# atxmega.net
KiCad netlist of a schematic drawn in Altium Designer
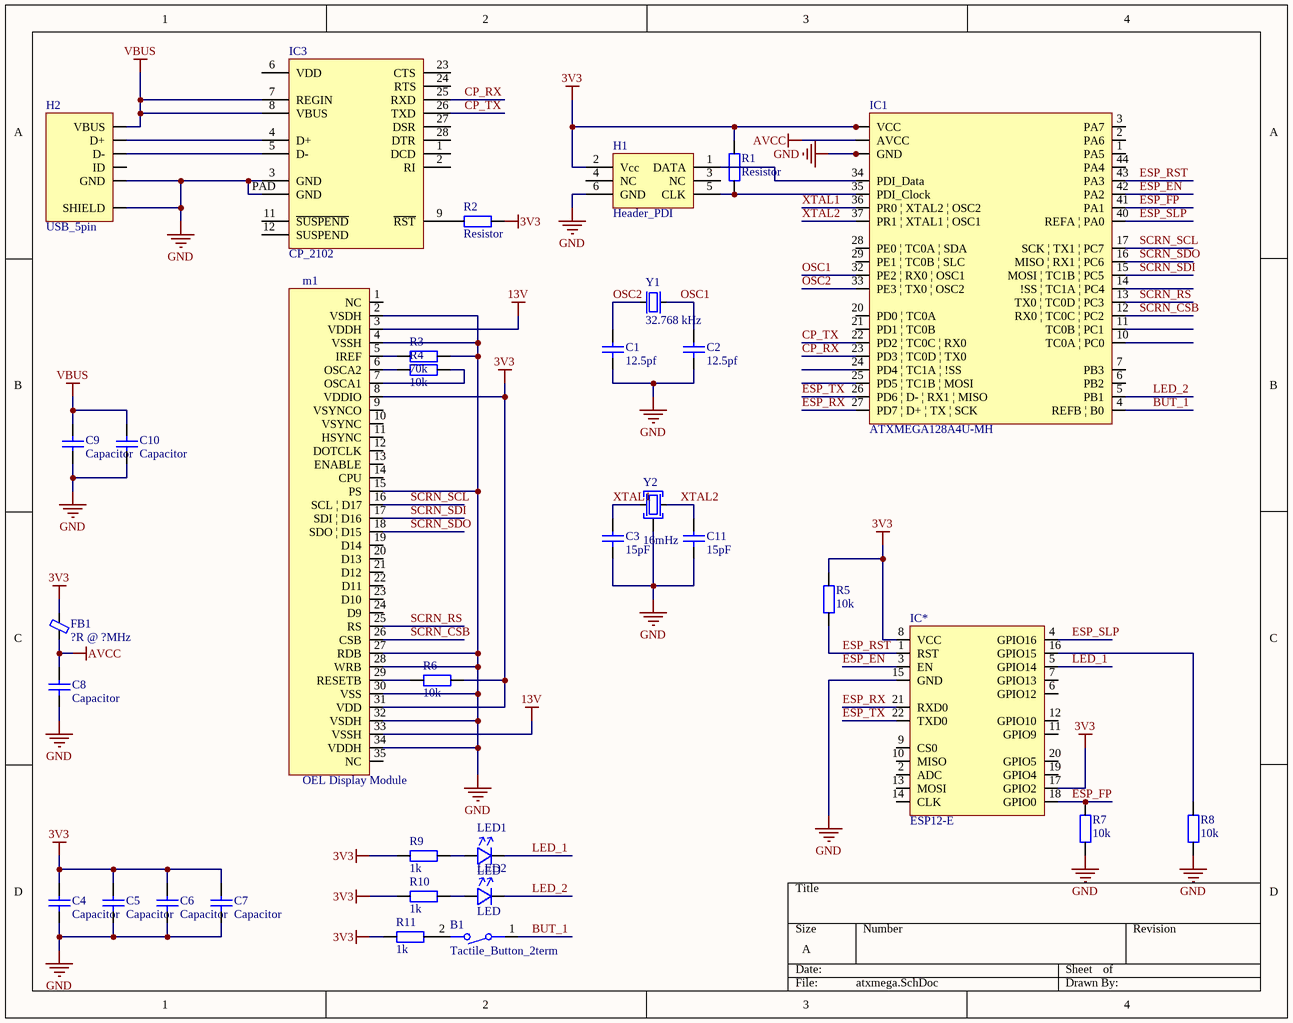
[diagram p0: atxmega.SchDoc]

(export (version "E")
  (design (tool "Eeschema 10.0.6"))
  (components
    (comp (ref "B1")
      (value "Tactile_Button_2term")
      (footprint "TACTILE_MINATUE_SMD_3.5x6mm")
      (libsource (lib "AranCustomFootprints") (part "Tactile_Button_2term"))
    )
    (comp (ref "C1")
      (value "12.5pf")
      (footprint "C0805")
      (description "Schematic symbol of a capacitor")
      (libsource (lib "AranCustomFootprints") (part "Capacitor"))
    )
    (comp (ref "C2")
      (value "12.5pf")
      (footprint "C0805")
      (description "Schematic symbol of a capacitor")
      (libsource (lib "AranCustomFootprints") (part "Capacitor"))
    )
    (comp (ref "C3")
      (value "15pF")
      (footprint "C0805")
      (description "Schematic symbol of a capacitor")
      (libsource (lib "AranCustomFootprints") (part "Capacitor"))
    )
    (comp (ref "C4")
      (value "Capacitor")
      (footprint "C0402")
      (description "Schematic symbol of a capacitor")
      (libsource (lib "AranCustomFootprints") (part "Capacitor"))
    )
    (comp (ref "C5")
      (value "Capacitor")
      (footprint "C0402")
      (description "Schematic symbol of a capacitor")
      (libsource (lib "AranCustomFootprints") (part "Capacitor"))
    )
    (comp (ref "C6")
      (value "Capacitor")
      (footprint "C0402")
      (description "Schematic symbol of a capacitor")
      (libsource (lib "AranCustomFootprints") (part "Capacitor"))
    )
    (comp (ref "C7")
      (value "Capacitor")
      (footprint "C0402")
      (description "Schematic symbol of a capacitor")
      (libsource (lib "AranCustomFootprints") (part "Capacitor"))
    )
    (comp (ref "C8")
      (value "Capacitor")
      (footprint "C0402")
      (description "Schematic symbol of a capacitor")
      (libsource (lib "AranCustomFootprints") (part "Capacitor"))
    )
    (comp (ref "C9")
      (value "Capacitor")
      (footprint "C0402")
      (description "Schematic symbol of a capacitor")
      (libsource (lib "AranCustomFootprints") (part "Capacitor"))
    )
    (comp (ref "C10")
      (value "Capacitor")
      (footprint "C0402")
      (description "Schematic symbol of a capacitor")
      (libsource (lib "AranCustomFootprints") (part "Capacitor"))
    )
    (comp (ref "C11")
      (value "15pF")
      (footprint "C0805")
      (description "Schematic symbol of a capacitor")
      (libsource (lib "AranCustomFootprints") (part "Capacitor"))
    )
    (comp (ref "FB1")
      (value "?R @ ?MHz")
      (footprint "L0805")
      (libsource (lib "AranCustomFootprints") (part "Ferrite"))
    )
    (comp (ref "H1")
      (value "Header_PDI")
      (footprint "6-HEADER_BOXED")
      (description "6-pin Boxed header with pinout used for PDI programming by Atmel programmers")
      (libsource (lib "AranCustomFootprints") (part "Header_PDI"))
    )
    (comp (ref "H2")
      (value "USB_5pin")
      (footprint "USB_Micro_B_RECEPTABLE_FCI")
      (description "5 Pins USB Connector")
      (libsource (lib "AranCustomFootprints") (part "USB_5pin"))
    )
    (comp (ref "IC*") (value "ESP12-E") (footprint "ESP12-E") (libsource (lib "elmarlib") (part "ESP12-E")))
    (comp (ref "IC1")
      (value "ATXMEGA128A4U-MH")
      (footprint "44-VFQFN-E")
      (description "AVR AVR® XMEGA® A4U Microcontroller IC 8/16-Bit 32MHz 128KB (64K x 16) FLASH 44-VQFN (7x7)")
      (libsource (lib "elmarlib") (part "ATXMEGA128A4U-MH"))
    )
    (comp (ref "IC3")
      (value "CP_2102")
      (footprint "28-QFN_Exposed_pad")
      (description "Single chip USB to UART Bridge")
      (libsource (lib "AranCustomFootprints") (part "CP_2102"))
    )
    (comp (ref "LED1")
      (value "LED")
      (footprint "0805_LED")
      (description "Schematic symbol of a LED")
      (libsource (lib "AranCustomFootprints") (part "LED"))
    )
    (comp (ref "LED2")
      (value "LED")
      (footprint "0805_LED")
      (description "Schematic symbol of a LED")
      (libsource (lib "AranCustomFootprints") (part "LED"))
    )
    (comp (ref "m1")
      (value "OEL Display Module")
      (footprint "FFC-35-pin-0.5")
      (description "Part ID: UG-6028GDEAF01")
      (libsource (lib "elmarlib") (part "OEL Display Module"))
    )
    (comp (ref "R1")
      (value "Resistor")
      (footprint "R0402")
      (description "Schematic symbol of a resistor")
      (libsource (lib "AranCustomFootprints") (part "Resistor"))
    )
    (comp (ref "R2")
      (value "Resistor")
      (footprint "R0402")
      (description "Schematic symbol of a resistor")
      (libsource (lib "AranCustomFootprints") (part "Resistor"))
    )
    (comp (ref "R3")
      (value "70k")
      (footprint "R0603")
      (description "Schematic symbol of a resistor")
      (libsource (lib "AranCustomFootprints") (part "Resistor"))
    )
    (comp (ref "R4")
      (value "10k")
      (footprint "R0603")
      (description "Schematic symbol of a resistor")
      (libsource (lib "AranCustomFootprints") (part "Resistor"))
    )
    (comp (ref "R5")
      (value "10k")
      (footprint "R0603")
      (description "Schematic symbol of a resistor")
      (libsource (lib "AranCustomFootprints") (part "Resistor"))
    )
    (comp (ref "R6")
      (value "10k")
      (footprint "R0603")
      (description "Schematic symbol of a resistor")
      (libsource (lib "AranCustomFootprints") (part "Resistor"))
    )
    (comp (ref "R7")
      (value "10k")
      (footprint "R0603")
      (description "Schematic symbol of a resistor")
      (libsource (lib "AranCustomFootprints") (part "Resistor"))
    )
    (comp (ref "R8")
      (value "10k")
      (footprint "R0603")
      (description "Schematic symbol of a resistor")
      (libsource (lib "AranCustomFootprints") (part "Resistor"))
    )
    (comp (ref "R9")
      (value "1k")
      (footprint "R0603")
      (description "Schematic symbol of a resistor")
      (libsource (lib "AranCustomFootprints") (part "Resistor"))
    )
    (comp (ref "R10")
      (value "1k")
      (footprint "R0603")
      (description "Schematic symbol of a resistor")
      (libsource (lib "AranCustomFootprints") (part "Resistor"))
    )
    (comp (ref "R11")
      (value "1k")
      (footprint "R0603")
      (description "Schematic symbol of a resistor")
      (libsource (lib "AranCustomFootprints") (part "Resistor"))
    )
    (comp (ref "Y1")
      (value "32.768 kHz")
      (footprint "4-SMD_FORK_CRYSTAL")
      (description "Schematic symbol of a 2pin crystal")
      (libsource (lib "AranCustomFootprints") (part "Crystal"))
    )
    (comp (ref "Y2")
      (value "16mHz")
      (footprint "Crystal_2.0x1.6")
      (description "Schematic symbol of a 2pin crystal with case connection")
      (libsource (lib "AranCustomFootprints") (part "Crystal_Ground"))
    )
  )
  (nets
    (net (code "1") (name "/BUT_1") (class "Default")
      (node (ref "B1") (pin "1") (pintype "passive"))
      (node (ref "IC1") (pin "4") (pinfunction "REFB_¦_B0_4") (pintype "passive"))
    )
    (net (code "2") (name "/CP_RX") (class "Default")
      (node (ref "IC1") (pin "23") (pinfunction "PD3_¦_TC0D_¦_TX0_23") (pintype "passive"))
      (node (ref "IC3") (pin "25") (pinfunction "RXD_25") (pintype "passive"))
    )
    (net (code "3") (name "/CP_TX") (class "Default")
      (node (ref "IC1") (pin "22") (pinfunction "PD2_¦_TC0C_¦_RX0_22") (pintype "passive"))
      (node (ref "IC3") (pin "26") (pinfunction "TXD_26") (pintype "passive"))
    )
    (net (code "4") (name "/ESP_EN") (class "Default")
      (node (ref "IC*") (pin "3") (pinfunction "EN_3") (pintype "passive"))
      (node (ref "IC1") (pin "42") (pinfunction "PA2_42") (pintype "passive"))
    )
    (net (code "5") (name "/ESP_FP") (class "Default")
      (node (ref "IC*") (pin "18") (pinfunction "GPIO0_18") (pintype "passive"))
      (node (ref "IC1") (pin "41") (pinfunction "PA1_41") (pintype "passive"))
      (node (ref "R7") (pin "1") (pinfunction "1_1") (pintype "passive"))
    )
    (net (code "6") (name "/ESP_RST") (class "Default")
      (node (ref "IC*") (pin "1") (pinfunction "RST_1") (pintype "passive"))
      (node (ref "IC1") (pin "43") (pinfunction "PA3_43") (pintype "passive"))
      (node (ref "R5") (pin "2") (pinfunction "2_2") (pintype "passive"))
    )
    (net (code "7") (name "/ESP_RX") (class "Default")
      (node (ref "IC*") (pin "21") (pinfunction "RXD0_21") (pintype "passive"))
      (node (ref "IC1") (pin "27") (pinfunction "PD7_¦_D+_¦_TX_¦_SCK_27") (pintype "passive"))
    )
    (net (code "8") (name "/ESP_SLP") (class "Default")
      (node (ref "IC*") (pin "4") (pinfunction "GPIO16_4") (pintype "passive"))
      (node (ref "IC1") (pin "40") (pinfunction "REFA_¦_PA0_40") (pintype "passive"))
    )
    (net (code "9") (name "/ESP_TX") (class "Default")
      (node (ref "IC*") (pin "22") (pinfunction "TXD0_22") (pintype "passive"))
      (node (ref "IC1") (pin "26") (pinfunction "PD6_¦_D-_¦_RX1_¦_MISO_26") (pintype "passive"))
    )
    (net (code "10") (name "/LED_1") (class "Default")
      (node (ref "IC*") (pin "5") (pinfunction "GPIO14_5") (pintype "passive"))
      (node (ref "LED1") (pin "C") (pinfunction "Cathode_C") (pintype "passive"))
    )
    (net (code "11") (name "/LED_2") (class "Default")
      (node (ref "IC1") (pin "5") (pinfunction "PB1_5") (pintype "passive"))
      (node (ref "LED2") (pin "C") (pinfunction "Cathode_C") (pintype "passive"))
    )
    (net (code "12") (name "/OSC1") (class "Default")
      (node (ref "C2") (pin "1") (pinfunction "1_1") (pintype "passive"))
      (node (ref "IC1") (pin "32") (pinfunction "PE2_¦_RX0_¦_OSC1_32") (pintype "passive"))
      (node (ref "Y1") (pin "1") (pinfunction "1_1") (pintype "passive"))
    )
    (net (code "13") (name "/OSC2") (class "Default")
      (node (ref "C1") (pin "1") (pinfunction "1_1") (pintype "passive"))
      (node (ref "IC1") (pin "33") (pinfunction "PE3_¦_TX0_¦_OSC2_33") (pintype "passive"))
      (node (ref "Y1") (pin "2") (pinfunction "2_2") (pintype "passive"))
    )
    (net (code "14") (name "/SCRN_CSB") (class "Default")
      (node (ref "IC1") (pin "12") (pinfunction "RX0_¦_TC0C_¦_PC2_12") (pintype "passive"))
      (node (ref "m1") (pin "26") (pinfunction "CSB_26") (pintype "passive"))
    )
    (net (code "15") (name "/SCRN_RS") (class "Default")
      (node (ref "IC1") (pin "13") (pinfunction "TX0_¦_TC0D_¦_PC3_13") (pintype "passive"))
      (node (ref "m1") (pin "25") (pinfunction "RS_25") (pintype "passive"))
    )
    (net (code "16") (name "/SCRN_SCL") (class "Default")
      (node (ref "IC1") (pin "17") (pinfunction "SCK_¦_TX1_¦_PC7_17") (pintype "passive"))
      (node (ref "m1") (pin "16") (pinfunction "SCL_¦_D17_16") (pintype "passive"))
    )
    (net (code "17") (name "/SCRN_SDI") (class "Default")
      (node (ref "IC1") (pin "15") (pinfunction "MOSI_¦_TC1B_¦_PC5_15") (pintype "passive"))
      (node (ref "m1") (pin "17") (pinfunction "SDI_¦_D16_17") (pintype "passive"))
    )
    (net (code "18") (name "/SCRN_SDO") (class "Default")
      (node (ref "IC1") (pin "16") (pinfunction "MISO_¦_RX1_¦_PC6_16") (pintype "passive"))
      (node (ref "m1") (pin "18") (pinfunction "SDO_¦_D15_18") (pintype "passive"))
    )
    (net (code "19") (name "/XTAL1") (class "Default")
      (node (ref "C3") (pin "1") (pinfunction "1_1") (pintype "passive"))
      (node (ref "IC1") (pin "36") (pinfunction "PR0_¦_XTAL2_¦_OSC2_36") (pintype "passive"))
      (node (ref "Y2") (pin "1") (pinfunction "1_1") (pintype "passive"))
    )
    (net (code "20") (name "/XTAL2") (class "Default")
      (node (ref "C11") (pin "1") (pinfunction "1_1") (pintype "passive"))
      (node (ref "IC1") (pin "37") (pinfunction "PR1_¦_XTAL1_¦_OSC1_37") (pintype "passive"))
      (node (ref "Y2") (pin "3") (pinfunction "3_3") (pintype "passive"))
    )
    (net (code "21") (name "3V3") (class "Default")
      (node (ref "C4") (pin "1") (pinfunction "1_1") (pintype "passive"))
      (node (ref "C5") (pin "1") (pinfunction "1_1") (pintype "passive"))
      (node (ref "C6") (pin "1") (pinfunction "1_1") (pintype "passive"))
      (node (ref "C7") (pin "1") (pinfunction "1_1") (pintype "passive"))
      (node (ref "FB1") (pin "2") (pinfunction "2_2") (pintype "passive"))
      (node (ref "H1") (pin "2") (pinfunction "Vcc_2") (pintype "passive"))
      (node (ref "IC*") (pin "17") (pinfunction "GPIO2_17") (pintype "passive"))
      (node (ref "IC*") (pin "8") (pinfunction "VCC_8") (pintype "passive"))
      (node (ref "IC1") (pin "19") (pinfunction "VCC_19") (pintype "passive"))
      (node (ref "IC1") (pin "31") (pinfunction "VCC_31") (pintype "passive"))
      (node (ref "IC1") (pin "9") (pinfunction "VCC_9") (pintype "passive"))
      (node (ref "R1") (pin "1") (pinfunction "1_1") (pintype "passive"))
      (node (ref "R10") (pin "1") (pinfunction "1_1") (pintype "passive"))
      (node (ref "R11") (pin "1") (pinfunction "1_1") (pintype "passive"))
      (node (ref "R2") (pin "1") (pinfunction "1_1") (pintype "passive"))
      (node (ref "R5") (pin "1") (pinfunction "1_1") (pintype "passive"))
      (node (ref "R6") (pin "1") (pinfunction "1_1") (pintype "passive"))
      (node (ref "R9") (pin "1") (pinfunction "1_1") (pintype "passive"))
      (node (ref "m1") (pin "31") (pinfunction "VDD_31") (pintype "passive"))
      (node (ref "m1") (pin "8") (pinfunction "VDDIO_8") (pintype "passive"))
    )
    (net (code "22") (name "13V") (class "Default")
      (node (ref "m1") (pin "3") (pinfunction "VDDH_3") (pintype "passive"))
      (node (ref "m1") (pin "33") (pinfunction "VSSH_33") (pintype "passive"))
    )
    (net (code "23") (name "AVCC") (class "Default")
      (node (ref "C8") (pin "1") (pinfunction "1_1") (pintype "passive"))
      (node (ref "FB1") (pin "1") (pinfunction "1_1") (pintype "passive"))
      (node (ref "IC1") (pin "39") (pinfunction "AVCC_39") (pintype "passive"))
    )
    (net (code "24") (name "GND") (class "Default")
      (node (ref "C1") (pin "2") (pinfunction "2_2") (pintype "passive"))
      (node (ref "C10") (pin "1") (pinfunction "1_1") (pintype "passive"))
      (node (ref "C11") (pin "2") (pinfunction "2_2") (pintype "passive"))
      (node (ref "C2") (pin "2") (pinfunction "2_2") (pintype "passive"))
      (node (ref "C3") (pin "2") (pinfunction "2_2") (pintype "passive"))
      (node (ref "C4") (pin "2") (pinfunction "2_2") (pintype "passive"))
      (node (ref "C5") (pin "2") (pinfunction "2_2") (pintype "passive"))
      (node (ref "C6") (pin "2") (pinfunction "2_2") (pintype "passive"))
      (node (ref "C7") (pin "2") (pinfunction "2_2") (pintype "passive"))
      (node (ref "C8") (pin "2") (pinfunction "2_2") (pintype "passive"))
      (node (ref "C9") (pin "1") (pinfunction "1_1") (pintype "passive"))
      (node (ref "H1") (pin "6") (pinfunction "GND_6") (pintype "passive"))
      (node (ref "H2") (pin "5") (pinfunction "GND_5") (pintype "passive"))
      (node (ref "H2") (pin "SHIELD") (pinfunction "SHIELD_SHIELD") (pintype "passive"))
      (node (ref "IC*") (pin "15") (pinfunction "GND_15") (pintype "passive"))
      (node (ref "IC1") (pin "18") (pinfunction "GND_18") (pintype "passive"))
      (node (ref "IC1") (pin "30") (pinfunction "GND_30") (pintype "passive"))
      (node (ref "IC1") (pin "38") (pinfunction "GND_38") (pintype "passive"))
      (node (ref "IC1") (pin "45") (pinfunction "GND_45") (pintype "passive"))
      (node (ref "IC1") (pin "8") (pinfunction "GND_8") (pintype "passive"))
      (node (ref "IC3") (pin "3") (pinfunction "GND_3") (pintype "passive"))
      (node (ref "IC3") (pin "PAD") (pinfunction "GND_PAD") (pintype "passive"))
      (node (ref "R3") (pin "1") (pinfunction "1_1") (pintype "passive"))
      (node (ref "R7") (pin "2") (pinfunction "2_2") (pintype "passive"))
      (node (ref "R8") (pin "2") (pinfunction "2_2") (pintype "passive"))
      (node (ref "Y2") (pin "2") (pinfunction "2_2") (pintype "passive"))
      (node (ref "m1") (pin "15") (pinfunction "PS_15") (pintype "passive"))
      (node (ref "m1") (pin "2") (pinfunction "VSDH_2") (pintype "passive"))
      (node (ref "m1") (pin "27") (pinfunction "RDB_27") (pintype "passive"))
      (node (ref "m1") (pin "28") (pinfunction "WRB_28") (pintype "passive"))
      (node (ref "m1") (pin "30") (pinfunction "VSS_30") (pintype "passive"))
      (node (ref "m1") (pin "32") (pinfunction "VSDH_32") (pintype "passive"))
      (node (ref "m1") (pin "34") (pinfunction "VDDH_34") (pintype "passive"))
      (node (ref "m1") (pin "4") (pinfunction "VSSH_4") (pintype "passive"))
    )
    (net (code "25") (name "Net-(B1-Pad2)") (class "Default")
      (node (ref "B1") (pin "2") (pintype "passive"))
      (node (ref "R11") (pin "2") (pinfunction "2_2") (pintype "passive"))
    )
    (net (code "26") (name "Net-(H1-CLK)") (class "Default")
      (node (ref "H1") (pin "5") (pinfunction "CLK_5") (pintype "passive"))
      (node (ref "IC1") (pin "35") (pinfunction "PDI_Clock_35") (pintype "passive"))
      (node (ref "R1") (pin "2") (pinfunction "2_2") (pintype "passive"))
    )
    (net (code "27") (name "Net-(H1-DATA)") (class "Default")
      (node (ref "H1") (pin "1") (pinfunction "DATA_1") (pintype "passive"))
      (node (ref "IC1") (pin "34") (pinfunction "PDI_Data_34") (pintype "passive"))
    )
    (net (code "28") (name "Net-(H2-D+)") (class "Default")
      (node (ref "H2") (pin "3") (pinfunction "D+_3") (pintype "passive"))
      (node (ref "IC3") (pin "4") (pinfunction "D+_4") (pintype "passive"))
    )
    (net (code "29") (name "Net-(H2-D-)") (class "Default")
      (node (ref "H2") (pin "2") (pinfunction "D-_2") (pintype "passive"))
      (node (ref "IC3") (pin "5") (pinfunction "D-_5") (pintype "passive"))
    )
    (net (code "30") (name "Net-(IC*-GPIO15)") (class "Default")
      (node (ref "IC*") (pin "16") (pinfunction "GPIO15_16") (pintype "passive"))
      (node (ref "R8") (pin "1") (pinfunction "1_1") (pintype "passive"))
    )
    (net (code "31") (name "Net-(IC3-~{RST})") (class "Default")
      (node (ref "IC3") (pin "9") (pinfunction "~{RST}_9") (pintype "passive"))
      (node (ref "R2") (pin "2") (pinfunction "2_2") (pintype "passive"))
    )
    (net (code "32") (name "Net-(LED1-Anode)") (class "Default")
      (node (ref "LED1") (pin "A") (pinfunction "Anode_A") (pintype "passive"))
      (node (ref "R9") (pin "2") (pinfunction "2_2") (pintype "passive"))
    )
    (net (code "33") (name "Net-(LED2-Anode)") (class "Default")
      (node (ref "LED2") (pin "A") (pinfunction "Anode_A") (pintype "passive"))
      (node (ref "R10") (pin "2") (pinfunction "2_2") (pintype "passive"))
    )
    (net (code "34") (name "Net-(m1-IREF)") (class "Default")
      (node (ref "R3") (pin "2") (pinfunction "2_2") (pintype "passive"))
      (node (ref "m1") (pin "5") (pinfunction "IREF_5") (pintype "passive"))
    )
    (net (code "35") (name "Net-(m1-OSCA1)") (class "Default")
      (node (ref "R4") (pin "1") (pinfunction "1_1") (pintype "passive"))
      (node (ref "m1") (pin "7") (pinfunction "OSCA1_7") (pintype "passive"))
    )
    (net (code "36") (name "Net-(m1-OSCA2)") (class "Default")
      (node (ref "R4") (pin "2") (pinfunction "2_2") (pintype "passive"))
      (node (ref "m1") (pin "6") (pinfunction "OSCA2_6") (pintype "passive"))
    )
    (net (code "37") (name "Net-(m1-RESETB)") (class "Default")
      (node (ref "R6") (pin "2") (pinfunction "2_2") (pintype "passive"))
      (node (ref "m1") (pin "29") (pinfunction "RESETB_29") (pintype "passive"))
    )
    (net (code "38") (name "VBUS") (class "Default")
      (node (ref "C10") (pin "2") (pinfunction "2_2") (pintype "passive"))
      (node (ref "C9") (pin "2") (pinfunction "2_2") (pintype "passive"))
      (node (ref "H2") (pin "1") (pinfunction "VBUS_1") (pintype "passive"))
      (node (ref "IC3") (pin "7") (pinfunction "REGIN_7") (pintype "passive"))
      (node (ref "IC3") (pin "8") (pinfunction "VBUS_8") (pintype "passive"))
    )
    (net (code "39") (name "unconnected-(H1-NC-Pad3)") (class "Default")
      (node (ref "H1") (pin "3") (pinfunction "NC_3") (pintype "passive"))
    )
    (net (code "40") (name "unconnected-(H1-NC-Pad4)") (class "Default")
      (node (ref "H1") (pin "4") (pinfunction "NC_4") (pintype "passive"))
    )
    (net (code "41") (name "unconnected-(H2-ID-Pad4)") (class "Default")
      (node (ref "H2") (pin "4") (pinfunction "ID_4") (pintype "passive"))
    )
    (net (code "42") (name "unconnected-(IC*-ADC-Pad2)") (class "Default")
      (node (ref "IC*") (pin "2") (pinfunction "ADC_2") (pintype "passive"))
    )
    (net (code "43") (name "unconnected-(IC*-CLK-Pad14)") (class "Default")
      (node (ref "IC*") (pin "14") (pinfunction "CLK_14") (pintype "passive"))
    )
    (net (code "44") (name "unconnected-(IC*-CS0-Pad9)") (class "Default")
      (node (ref "IC*") (pin "9") (pinfunction "CS0_9") (pintype "passive"))
    )
    (net (code "45") (name "unconnected-(IC*-GPIO4-Pad19)") (class "Default")
      (node (ref "IC*") (pin "19") (pinfunction "GPIO4_19") (pintype "passive"))
    )
    (net (code "46") (name "unconnected-(IC*-GPIO5-Pad20)") (class "Default")
      (node (ref "IC*") (pin "20") (pinfunction "GPIO5_20") (pintype "passive"))
    )
    (net (code "47") (name "unconnected-(IC*-GPIO9-Pad11)") (class "Default")
      (node (ref "IC*") (pin "11") (pinfunction "GPIO9_11") (pintype "passive"))
    )
    (net (code "48") (name "unconnected-(IC*-GPIO10-Pad12)") (class "Default")
      (node (ref "IC*") (pin "12") (pinfunction "GPIO10_12") (pintype "passive"))
    )
    (net (code "49") (name "unconnected-(IC*-GPIO12-Pad6)") (class "Default")
      (node (ref "IC*") (pin "6") (pinfunction "GPIO12_6") (pintype "passive"))
    )
    (net (code "50") (name "unconnected-(IC*-GPIO13-Pad7)") (class "Default")
      (node (ref "IC*") (pin "7") (pinfunction "GPIO13_7") (pintype "passive"))
    )
    (net (code "51") (name "unconnected-(IC*-MISO-Pad10)") (class "Default")
      (node (ref "IC*") (pin "10") (pinfunction "MISO_10") (pintype "passive"))
    )
    (net (code "52") (name "unconnected-(IC*-MOSI-Pad13)") (class "Default")
      (node (ref "IC*") (pin "13") (pinfunction "MOSI_13") (pintype "passive"))
    )
    (net (code "53") (name "unconnected-(IC1-!SS_¦_TC1A_¦_PC4-Pad14)") (class "Default")
      (node (ref "IC1") (pin "14") (pinfunction "!SS_¦_TC1A_¦_PC4_14") (pintype "passive"))
    )
    (net (code "54") (name "unconnected-(IC1-PA4-Pad44)") (class "Default")
      (node (ref "IC1") (pin "44") (pinfunction "PA4_44") (pintype "passive"))
    )
    (net (code "55") (name "unconnected-(IC1-PA5-Pad1)") (class "Default")
      (node (ref "IC1") (pin "1") (pinfunction "PA5_1") (pintype "passive"))
    )
    (net (code "56") (name "unconnected-(IC1-PA6-Pad2)") (class "Default")
      (node (ref "IC1") (pin "2") (pinfunction "PA6_2") (pintype "passive"))
    )
    (net (code "57") (name "unconnected-(IC1-PA7-Pad3)") (class "Default")
      (node (ref "IC1") (pin "3") (pinfunction "PA7_3") (pintype "passive"))
    )
    (net (code "58") (name "unconnected-(IC1-PB2-Pad6)") (class "Default")
      (node (ref "IC1") (pin "6") (pinfunction "PB2_6") (pintype "passive"))
    )
    (net (code "59") (name "unconnected-(IC1-PB3-Pad7)") (class "Default")
      (node (ref "IC1") (pin "7") (pinfunction "PB3_7") (pintype "passive"))
    )
    (net (code "60") (name "unconnected-(IC1-PD0_¦_TC0A-Pad20)") (class "Default")
      (node (ref "IC1") (pin "20") (pinfunction "PD0_¦_TC0A_20") (pintype "passive"))
    )
    (net (code "61") (name "unconnected-(IC1-PD1_¦_TC0B-Pad21)") (class "Default")
      (node (ref "IC1") (pin "21") (pinfunction "PD1_¦_TC0B_21") (pintype "passive"))
    )
    (net (code "62") (name "unconnected-(IC1-PD4_¦_TC1A_¦_!SS-Pad24)") (class "Default")
      (node (ref "IC1") (pin "24") (pinfunction "PD4_¦_TC1A_¦_!SS_24") (pintype "passive"))
    )
    (net (code "63") (name "unconnected-(IC1-PD5_¦_TC1B_¦_MOSI-Pad25)") (class "Default")
      (node (ref "IC1") (pin "25") (pinfunction "PD5_¦_TC1B_¦_MOSI_25") (pintype "passive"))
    )
    (net (code "64") (name "unconnected-(IC1-PE0_¦_TC0A_¦_SDA-Pad28)") (class "Default")
      (node (ref "IC1") (pin "28") (pinfunction "PE0_¦_TC0A_¦_SDA_28") (pintype "passive"))
    )
    (net (code "65") (name "unconnected-(IC1-PE1_¦_TC0B_¦_SLC-Pad29)") (class "Default")
      (node (ref "IC1") (pin "29") (pinfunction "PE1_¦_TC0B_¦_SLC_29") (pintype "passive"))
    )
    (net (code "66") (name "unconnected-(IC1-TC0A_¦_PC0-Pad10)") (class "Default")
      (node (ref "IC1") (pin "10") (pinfunction "TC0A_¦_PC0_10") (pintype "passive"))
    )
    (net (code "67") (name "unconnected-(IC1-TC0B_¦_PC1-Pad11)") (class "Default")
      (node (ref "IC1") (pin "11") (pinfunction "TC0B_¦_PC1_11") (pintype "passive"))
    )
    (net (code "68") (name "unconnected-(IC3-CTS-Pad23)") (class "Default")
      (node (ref "IC3") (pin "23") (pinfunction "CTS_23") (pintype "passive"))
    )
    (net (code "69") (name "unconnected-(IC3-DCD-Pad1)") (class "Default")
      (node (ref "IC3") (pin "1") (pinfunction "DCD_1") (pintype "passive"))
    )
    (net (code "70") (name "unconnected-(IC3-DSR-Pad27)") (class "Default")
      (node (ref "IC3") (pin "27") (pinfunction "DSR_27") (pintype "passive"))
    )
    (net (code "71") (name "unconnected-(IC3-DTR-Pad28)") (class "Default")
      (node (ref "IC3") (pin "28") (pinfunction "DTR_28") (pintype "passive"))
    )
    (net (code "72") (name "unconnected-(IC3-RI-Pad2)") (class "Default")
      (node (ref "IC3") (pin "2") (pinfunction "RI_2") (pintype "passive"))
    )
    (net (code "73") (name "unconnected-(IC3-RTS-Pad24)") (class "Default")
      (node (ref "IC3") (pin "24") (pinfunction "RTS_24") (pintype "passive"))
    )
    (net (code "74") (name "unconnected-(IC3-SUSPEND-Pad12)") (class "Default")
      (node (ref "IC3") (pin "12") (pinfunction "SUSPEND_12") (pintype "passive"))
    )
    (net (code "75") (name "unconnected-(IC3-VDD-Pad6)") (class "Default")
      (node (ref "IC3") (pin "6") (pinfunction "VDD_6") (pintype "passive"))
    )
    (net (code "76") (name "unconnected-(IC3-~{SUSPEND}-Pad11)") (class "Default")
      (node (ref "IC3") (pin "11") (pinfunction "~{SUSPEND}_11") (pintype "passive"))
    )
    (net (code "77") (name "unconnected-(m1-CPU-Pad14)") (class "Default")
      (node (ref "m1") (pin "14") (pinfunction "CPU_14") (pintype "passive"))
    )
    (net (code "78") (name "unconnected-(m1-D9-Pad24)") (class "Default")
      (node (ref "m1") (pin "24") (pinfunction "D9_24") (pintype "passive"))
    )
    (net (code "79") (name "unconnected-(m1-D10-Pad23)") (class "Default")
      (node (ref "m1") (pin "23") (pinfunction "D10_23") (pintype "passive"))
    )
    (net (code "80") (name "unconnected-(m1-D11-Pad22)") (class "Default")
      (node (ref "m1") (pin "22") (pinfunction "D11_22") (pintype "passive"))
    )
    (net (code "81") (name "unconnected-(m1-D12-Pad21)") (class "Default")
      (node (ref "m1") (pin "21") (pinfunction "D12_21") (pintype "passive"))
    )
    (net (code "82") (name "unconnected-(m1-D13-Pad20)") (class "Default")
      (node (ref "m1") (pin "20") (pinfunction "D13_20") (pintype "passive"))
    )
    (net (code "83") (name "unconnected-(m1-D14-Pad19)") (class "Default")
      (node (ref "m1") (pin "19") (pinfunction "D14_19") (pintype "passive"))
    )
    (net (code "84") (name "unconnected-(m1-DOTCLK-Pad12)") (class "Default")
      (node (ref "m1") (pin "12") (pinfunction "DOTCLK_12") (pintype "passive"))
    )
    (net (code "85") (name "unconnected-(m1-ENABLE-Pad13)") (class "Default")
      (node (ref "m1") (pin "13") (pinfunction "ENABLE_13") (pintype "passive"))
    )
    (net (code "86") (name "unconnected-(m1-HSYNC-Pad11)") (class "Default")
      (node (ref "m1") (pin "11") (pinfunction "HSYNC_11") (pintype "passive"))
    )
    (net (code "87") (name "unconnected-(m1-NC-Pad1)") (class "Default")
      (node (ref "m1") (pin "1") (pinfunction "NC_1") (pintype "passive"))
    )
    (net (code "88") (name "unconnected-(m1-NC-Pad35)") (class "Default")
      (node (ref "m1") (pin "35") (pinfunction "NC_35") (pintype "passive"))
    )
    (net (code "89") (name "unconnected-(m1-VSYNC-Pad10)") (class "Default")
      (node (ref "m1") (pin "10") (pinfunction "VSYNC_10") (pintype "passive"))
    )
    (net (code "90") (name "unconnected-(m1-VSYNCO-Pad9)") (class "Default")
      (node (ref "m1") (pin "9") (pinfunction "VSYNCO_9") (pintype "passive"))
    )
  )
)
